# PLL_Controller_STM32.net
KiCad netlist of a schematic drawn in Altium Designer
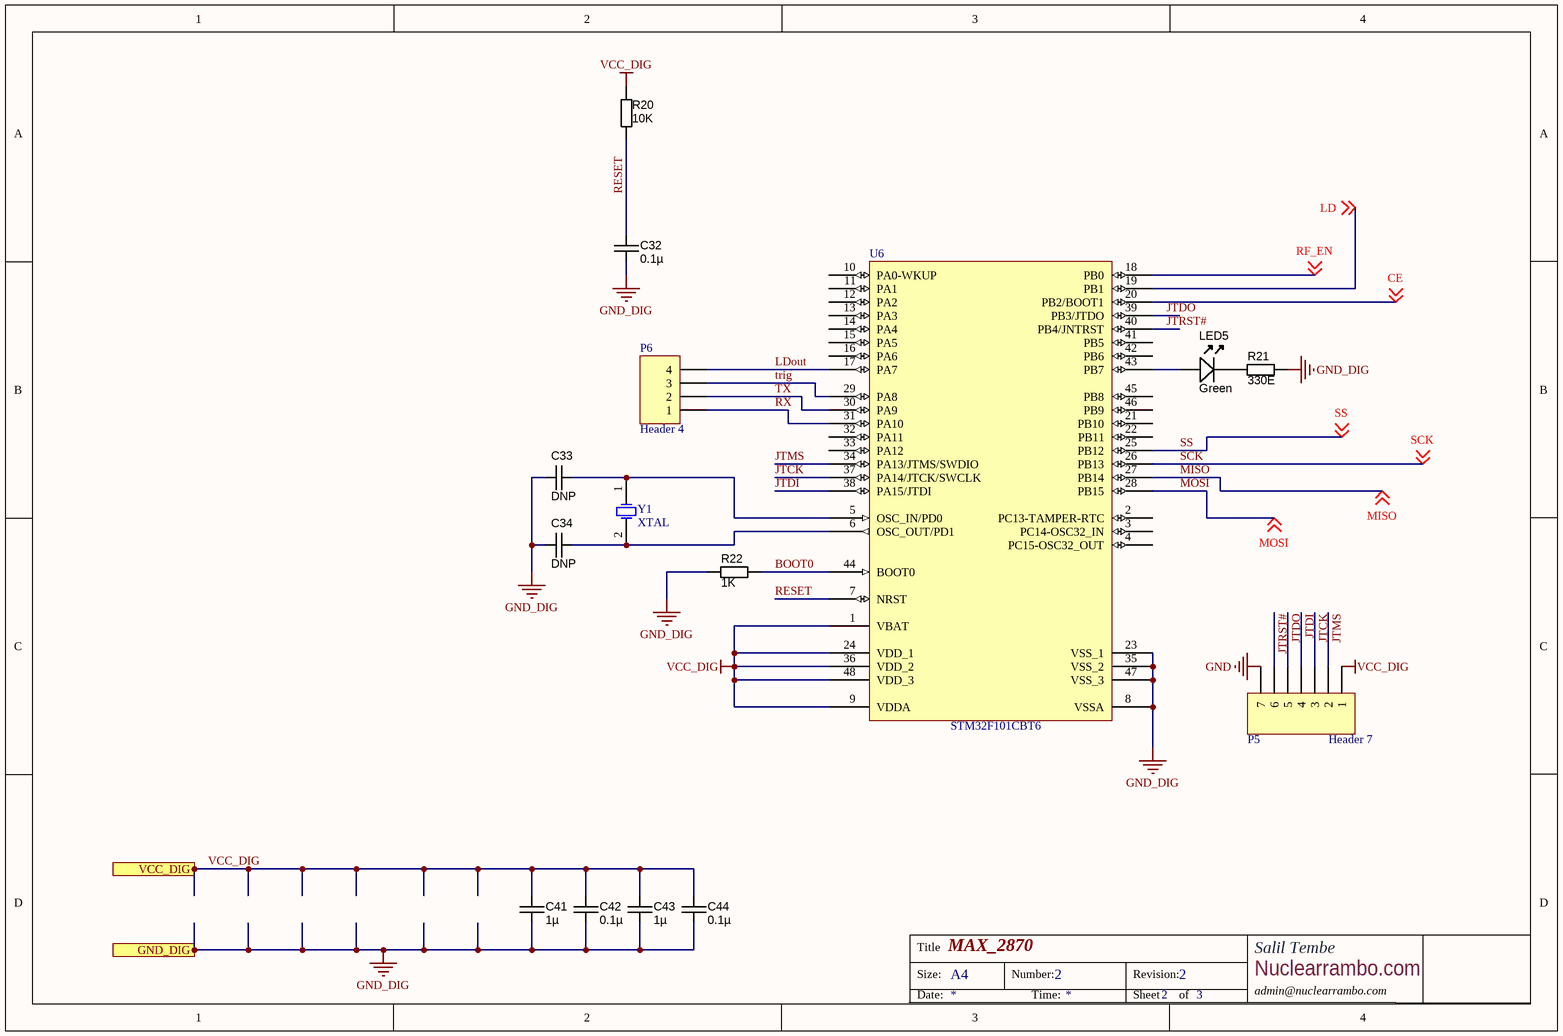
[diagram p0: PLL_Controller_STM32.SchDoc]

(export (version "E")
  (design (tool "Eeschema 10.0.6"))
  (components
    (comp (ref "C32")
      (value "0.1µ")
      (footprint "CAPC2012X135N")
      (description "Capacitor SMD Cer 10uF 10% 10V X5R 0805")
      (fields (field (name "TOLERANCE") "±10%") (field (name "Comment") "approved sub OK"))
      (libsource (lib "PBL - Capacitors") (part "CAPC_10u_0805_10V"))
    )
    (comp (ref "C33")
      (value "DNP")
      (footprint "CAPC2012X135N")
      (description "Capacitor SMD Cer 10uF 10% 10V X5R 0805")
      (fields (field (name "TOLERANCE") "±10%") (field (name "Comment") "approved sub OK"))
      (libsource (lib "PBL - Capacitors") (part "CAPC_10u_0805_10V"))
    )
    (comp (ref "C34")
      (value "DNP")
      (footprint "CAPC2012X135N")
      (description "Capacitor SMD Cer 10uF 10% 10V X5R 0805")
      (fields (field (name "TOLERANCE") "±10%") (field (name "Comment") "approved sub OK"))
      (libsource (lib "PBL - Capacitors") (part "CAPC_10u_0805_10V"))
    )
    (comp (ref "C41")
      (value "1µ")
      (footprint "CAPC2012X135N")
      (description "Capacitor SMD Cer 10uF 10% 10V X5R 0805")
      (fields (field (name "TOLERANCE") "±10%") (field (name "Comment") "approved sub OK"))
      (libsource (lib "PBL - Capacitors") (part "CAPC_10u_0805_10V"))
    )
    (comp (ref "C42")
      (value "0.1µ")
      (footprint "CAPC2012X135N")
      (description "Capacitor SMD Cer 10uF 10% 10V X5R 0805")
      (fields (field (name "TOLERANCE") "±10%") (field (name "Comment") "approved sub OK"))
      (libsource (lib "PBL - Capacitors") (part "CAPC_10u_0805_10V"))
    )
    (comp (ref "C43")
      (value "1µ")
      (footprint "CAPC2012X135N")
      (description "Capacitor SMD Cer 10uF 10% 10V X5R 0805")
      (fields (field (name "TOLERANCE") "±10%") (field (name "Comment") "approved sub OK"))
      (libsource (lib "PBL - Capacitors") (part "CAPC_10u_0805_10V"))
    )
    (comp (ref "C44")
      (value "0.1µ")
      (footprint "CAPC2012X135N")
      (description "Capacitor SMD Cer 10uF 10% 10V X5R 0805")
      (fields (field (name "TOLERANCE") "±10%") (field (name "Comment") "approved sub OK"))
      (libsource (lib "PBL - Capacitors") (part "CAPC_10u_0805_10V"))
    )
    (comp (ref "LED5")
      (value "Green")
      (footprint "LED-0603-GREEN")
      (description "LED 0603 SMD Green 570nm 50mcd 20mA")
      (libsource (lib "PBL - Light Sources") (part "LED_SMD_Green_0603_570nm"))
    )
    (comp (ref "P5")
      (value "Header 7")
      (footprint "HDR1X7")
      (description "Header, 7-Pin")
      (fields (field (name "PUBLISHER") "Altium Limited"))
      (libsource (lib "Miscellaneous Connectors") (part "Header 7"))
    )
    (comp (ref "P6")
      (value "Header 4")
      (footprint "HDR1X4")
      (description "Header, 4-Pin")
      (fields (field (name "PUBLISHER") "Altium Limited"))
      (libsource (lib "Miscellaneous Connectors") (part "Header 4"))
    )
    (comp (ref "R20")
      (value "10K")
      (footprint "RESC1005X40N")
      (description "Resistor SMD chip 1k Ohm 0.063W 5% 0402")
      (fields (field (name "TOLERANCE") "±5%") (field (name "Comment") "Thick Film"))
      (libsource (lib "PBL - Resistors") (part "RES_1K_0402_5%"))
    )
    (comp (ref "R21")
      (value "330E")
      (footprint "RESC1005X40N")
      (description "Resistor SMD chip 1k Ohm 0.063W 5% 0402")
      (fields (field (name "TOLERANCE") "±5%") (field (name "Comment") "Thick Film"))
      (libsource (lib "") (part "RES_1K_0402_5%_1"))
    )
    (comp (ref "R22")
      (value "1K")
      (footprint "RESC1005X40N")
      (description "Resistor SMD chip 1k Ohm 0.063W 5% 0402")
      (fields (field (name "TOLERANCE") "±5%") (field (name "Comment") "Thick Film"))
      (libsource (lib "") (part "RES_1K_0402_5%_1"))
    )
    (comp (ref "U6")
      (value "STM32F101CBT6")
      (footprint "LQFP48_N")
      (description "STM32 ARM-based 32-bit MCU with 128 Kbytes Flash, 48-pin LQFP, Industrial Temperature")
      (fields (field (name "PUBLISHER") "Altium Limited"))
      (libsource (lib "ST Microcontroller 32-Bit STM32") (part "STM32F101CBT6"))
    )
    (comp (ref "Y1")
      (value "XTAL")
      (footprint "R38")
      (description "Crystal Oscillator")
      (fields (field (name "PUBLISHER") "Altium Limited"))
      (libsource (lib "Miscellaneous Devices") (part "XTAL"))
    )
  )
  (nets
    (net (code "2") (name "/BOOT0") (class "Default")
      (node (ref "R22") (pin "2") (pinfunction "2_2") (pintype "passive"))
      (node (ref "U6") (pin "44") (pinfunction "BOOT0_44") (pintype "input"))
    )
    (net (code "3") (name "/JTCK") (class "Default")
      (node (ref "P5") (pin "3") (pinfunction "3_3") (pintype "passive"))
      (node (ref "U6") (pin "37") (pinfunction "PA14/JTCK/SWCLK_37") (pintype "bidirectional"))
    )
    (net (code "4") (name "/JTDI") (class "Default")
      (node (ref "P5") (pin "4") (pinfunction "4_4") (pintype "passive"))
      (node (ref "U6") (pin "38") (pinfunction "PA15/JTDI_38") (pintype "bidirectional"))
    )
    (net (code "5") (name "/JTDO") (class "Default")
      (node (ref "P5") (pin "5") (pinfunction "5_5") (pintype "passive"))
      (node (ref "U6") (pin "39") (pinfunction "PB3/JTDO_39") (pintype "bidirectional"))
    )
    (net (code "6") (name "/JTMS") (class "Default")
      (node (ref "P5") (pin "2") (pinfunction "2_2") (pintype "passive"))
      (node (ref "U6") (pin "34") (pinfunction "PA13/JTMS/SWDIO_34") (pintype "bidirectional"))
    )
    (net (code "7") (name "/JTRST#") (class "Default")
      (node (ref "P5") (pin "6") (pinfunction "6_6") (pintype "passive"))
      (node (ref "U6") (pin "40") (pinfunction "PB4/JNTRST_40") (pintype "bidirectional"))
    )
    (net (code "8") (name "/LDout") (class "Default")
      (node (ref "P6") (pin "4") (pinfunction "4_4") (pintype "passive"))
      (node (ref "U6") (pin "17") (pinfunction "PA7_17") (pintype "bidirectional"))
    )
    (net (code "9") (name "/RESET") (class "Default")
      (node (ref "C32") (pin "2") (pintype "passive"))
      (node (ref "R20") (pin "1") (pinfunction "1_1") (pintype "passive"))
      (node (ref "U6") (pin "7") (pinfunction "NRST_7") (pintype "bidirectional"))
    )
    (net (code "10") (name "/RX") (class "Default")
      (node (ref "P6") (pin "1") (pinfunction "1_1") (pintype "passive"))
      (node (ref "U6") (pin "31") (pinfunction "PA10_31") (pintype "bidirectional"))
    )
    (net (code "11") (name "/TX") (class "Default")
      (node (ref "P6") (pin "2") (pinfunction "2_2") (pintype "passive"))
      (node (ref "U6") (pin "30") (pinfunction "PA9_30") (pintype "bidirectional"))
    )
    (net (code "12") (name "/trig") (class "Default")
      (node (ref "P6") (pin "3") (pinfunction "3_3") (pintype "passive"))
      (node (ref "U6") (pin "29") (pinfunction "PA8_29") (pintype "bidirectional"))
    )
    (net (code "13") (name "CE") (class "Default")
      (node (ref "U6") (pin "20") (pinfunction "PB2/BOOT1_20") (pintype "bidirectional"))
    )
    (net (code "14") (name "GND") (class "Default")
      (node (ref "P5") (pin "7") (pinfunction "7_7") (pintype "passive"))
    )
    (net (code "15") (name "GND_DIG") (class "Default")
      (node (ref "C32") (pin "1") (pintype "passive"))
      (node (ref "C33") (pin "1") (pintype "passive"))
      (node (ref "C34") (pin "1") (pintype "passive"))
      (node (ref "C41") (pin "1") (pintype "passive"))
      (node (ref "C42") (pin "1") (pintype "passive"))
      (node (ref "C43") (pin "1") (pintype "passive"))
      (node (ref "C44") (pin "1") (pintype "passive"))
      (node (ref "R21") (pin "2") (pinfunction "2_2") (pintype "passive"))
      (node (ref "R22") (pin "1") (pinfunction "1_1") (pintype "passive"))
      (node (ref "U6") (pin "23") (pinfunction "VSS_1_23") (pintype "power_in"))
      (node (ref "U6") (pin "35") (pinfunction "VSS_2_35") (pintype "power_in"))
      (node (ref "U6") (pin "47") (pinfunction "VSS_3_47") (pintype "power_in"))
      (node (ref "U6") (pin "8") (pinfunction "VSSA_8") (pintype "power_in"))
    )
    (net (code "16") (name "LD") (class "Default")
      (node (ref "U6") (pin "19") (pinfunction "PB1_19") (pintype "bidirectional"))
    )
    (net (code "17") (name "MISO") (class "Default")
      (node (ref "U6") (pin "27") (pinfunction "PB14_27") (pintype "bidirectional"))
    )
    (net (code "18") (name "MOSI") (class "Default")
      (node (ref "U6") (pin "28") (pinfunction "PB15_28") (pintype "bidirectional"))
    )
    (net (code "19") (name "Net-(LED5-PadK)") (class "Default")
      (node (ref "LED5") (pin "K") (pinfunction "K_K") (pintype "passive"))
      (node (ref "R21") (pin "1") (pinfunction "1_1") (pintype "passive"))
    )
    (net (code "20") (name "Net-(U6-OSC_IN{slash}PD0)") (class "Default")
      (node (ref "C33") (pin "2") (pintype "passive"))
      (node (ref "U6") (pin "5") (pinfunction "OSC_IN/PD0_5") (pintype "input"))
      (node (ref "Y1") (pin "1") (pinfunction "OSC1_1") (pintype "passive"))
    )
    (net (code "21") (name "Net-(U6-OSC_OUT{slash}PD1)") (class "Default")
      (node (ref "C34") (pin "2") (pintype "passive"))
      (node (ref "U6") (pin "6") (pinfunction "OSC_OUT/PD1_6") (pintype "output"))
      (node (ref "Y1") (pin "2") (pinfunction "OSC2_2") (pintype "passive"))
    )
    (net (code "22") (name "Net-(U6-PB7)") (class "Default")
      (node (ref "LED5") (pin "A") (pinfunction "A_A") (pintype "passive"))
      (node (ref "U6") (pin "43") (pinfunction "PB7_43") (pintype "bidirectional"))
    )
    (net (code "23") (name "RF_EN") (class "Default")
      (node (ref "U6") (pin "18") (pinfunction "PB0_18") (pintype "bidirectional"))
    )
    (net (code "24") (name "SCK") (class "Default")
      (node (ref "U6") (pin "26") (pinfunction "PB13_26") (pintype "bidirectional"))
    )
    (net (code "25") (name "SS") (class "Default")
      (node (ref "U6") (pin "25") (pinfunction "PB12_25") (pintype "bidirectional"))
    )
    (net (code "26") (name "VCC_DIG") (class "Default")
      (node (ref "C41") (pin "2") (pintype "passive"))
      (node (ref "C42") (pin "2") (pintype "passive"))
      (node (ref "C43") (pin "2") (pintype "passive"))
      (node (ref "C44") (pin "2") (pintype "passive"))
      (node (ref "P5") (pin "1") (pinfunction "1_1") (pintype "passive"))
      (node (ref "R20") (pin "2") (pinfunction "2_2") (pintype "passive"))
      (node (ref "U6") (pin "1") (pinfunction "VBAT_1") (pintype "power_in"))
      (node (ref "U6") (pin "24") (pinfunction "VDD_1_24") (pintype "power_in"))
      (node (ref "U6") (pin "36") (pinfunction "VDD_2_36") (pintype "power_in"))
      (node (ref "U6") (pin "48") (pinfunction "VDD_3_48") (pintype "power_in"))
      (node (ref "U6") (pin "9") (pinfunction "VDDA_9") (pintype "power_in"))
    )
    (net (code "27") (name "unconnected-(U6-PA0-WKUP-Pad10)") (class "Default")
      (node (ref "U6") (pin "10") (pinfunction "PA0-WKUP_10") (pintype "bidirectional"))
    )
    (net (code "28") (name "unconnected-(U6-PA1-Pad11)") (class "Default")
      (node (ref "U6") (pin "11") (pinfunction "PA1_11") (pintype "bidirectional"))
    )
    (net (code "29") (name "unconnected-(U6-PA2-Pad12)") (class "Default")
      (node (ref "U6") (pin "12") (pinfunction "PA2_12") (pintype "bidirectional"))
    )
    (net (code "30") (name "unconnected-(U6-PA3-Pad13)") (class "Default")
      (node (ref "U6") (pin "13") (pinfunction "PA3_13") (pintype "bidirectional"))
    )
    (net (code "31") (name "unconnected-(U6-PA4-Pad14)") (class "Default")
      (node (ref "U6") (pin "14") (pinfunction "PA4_14") (pintype "bidirectional"))
    )
    (net (code "32") (name "unconnected-(U6-PA5-Pad15)") (class "Default")
      (node (ref "U6") (pin "15") (pinfunction "PA5_15") (pintype "bidirectional"))
    )
    (net (code "33") (name "unconnected-(U6-PA6-Pad16)") (class "Default")
      (node (ref "U6") (pin "16") (pinfunction "PA6_16") (pintype "bidirectional"))
    )
    (net (code "34") (name "unconnected-(U6-PA11-Pad32)") (class "Default")
      (node (ref "U6") (pin "32") (pinfunction "PA11_32") (pintype "bidirectional"))
    )
    (net (code "35") (name "unconnected-(U6-PA12-Pad33)") (class "Default")
      (node (ref "U6") (pin "33") (pinfunction "PA12_33") (pintype "bidirectional"))
    )
    (net (code "36") (name "unconnected-(U6-PB5-Pad41)") (class "Default")
      (node (ref "U6") (pin "41") (pinfunction "PB5_41") (pintype "bidirectional"))
    )
    (net (code "37") (name "unconnected-(U6-PB6-Pad42)") (class "Default")
      (node (ref "U6") (pin "42") (pinfunction "PB6_42") (pintype "bidirectional"))
    )
    (net (code "38") (name "unconnected-(U6-PB8-Pad45)") (class "Default")
      (node (ref "U6") (pin "45") (pinfunction "PB8_45") (pintype "bidirectional"))
    )
    (net (code "39") (name "unconnected-(U6-PB9-Pad46)") (class "Default")
      (node (ref "U6") (pin "46") (pinfunction "PB9_46") (pintype "bidirectional"))
    )
    (net (code "40") (name "unconnected-(U6-PB10-Pad21)") (class "Default")
      (node (ref "U6") (pin "21") (pinfunction "PB10_21") (pintype "bidirectional"))
    )
    (net (code "41") (name "unconnected-(U6-PB11-Pad22)") (class "Default")
      (node (ref "U6") (pin "22") (pinfunction "PB11_22") (pintype "bidirectional"))
    )
    (net (code "42") (name "unconnected-(U6-PC13-TAMPER-RTC-Pad2)") (class "Default")
      (node (ref "U6") (pin "2") (pinfunction "PC13-TAMPER-RTC_2") (pintype "bidirectional"))
    )
    (net (code "43") (name "unconnected-(U6-PC14-OSC32_IN-Pad3)") (class "Default")
      (node (ref "U6") (pin "3") (pinfunction "PC14-OSC32_IN_3") (pintype "bidirectional"))
    )
    (net (code "44") (name "unconnected-(U6-PC15-OSC32_OUT-Pad4)") (class "Default")
      (node (ref "U6") (pin "4") (pinfunction "PC15-OSC32_OUT_4") (pintype "bidirectional"))
    )
  )
)
